# m80-v0_01.net
KiCad netlist of a schematic drawn in EAGLE
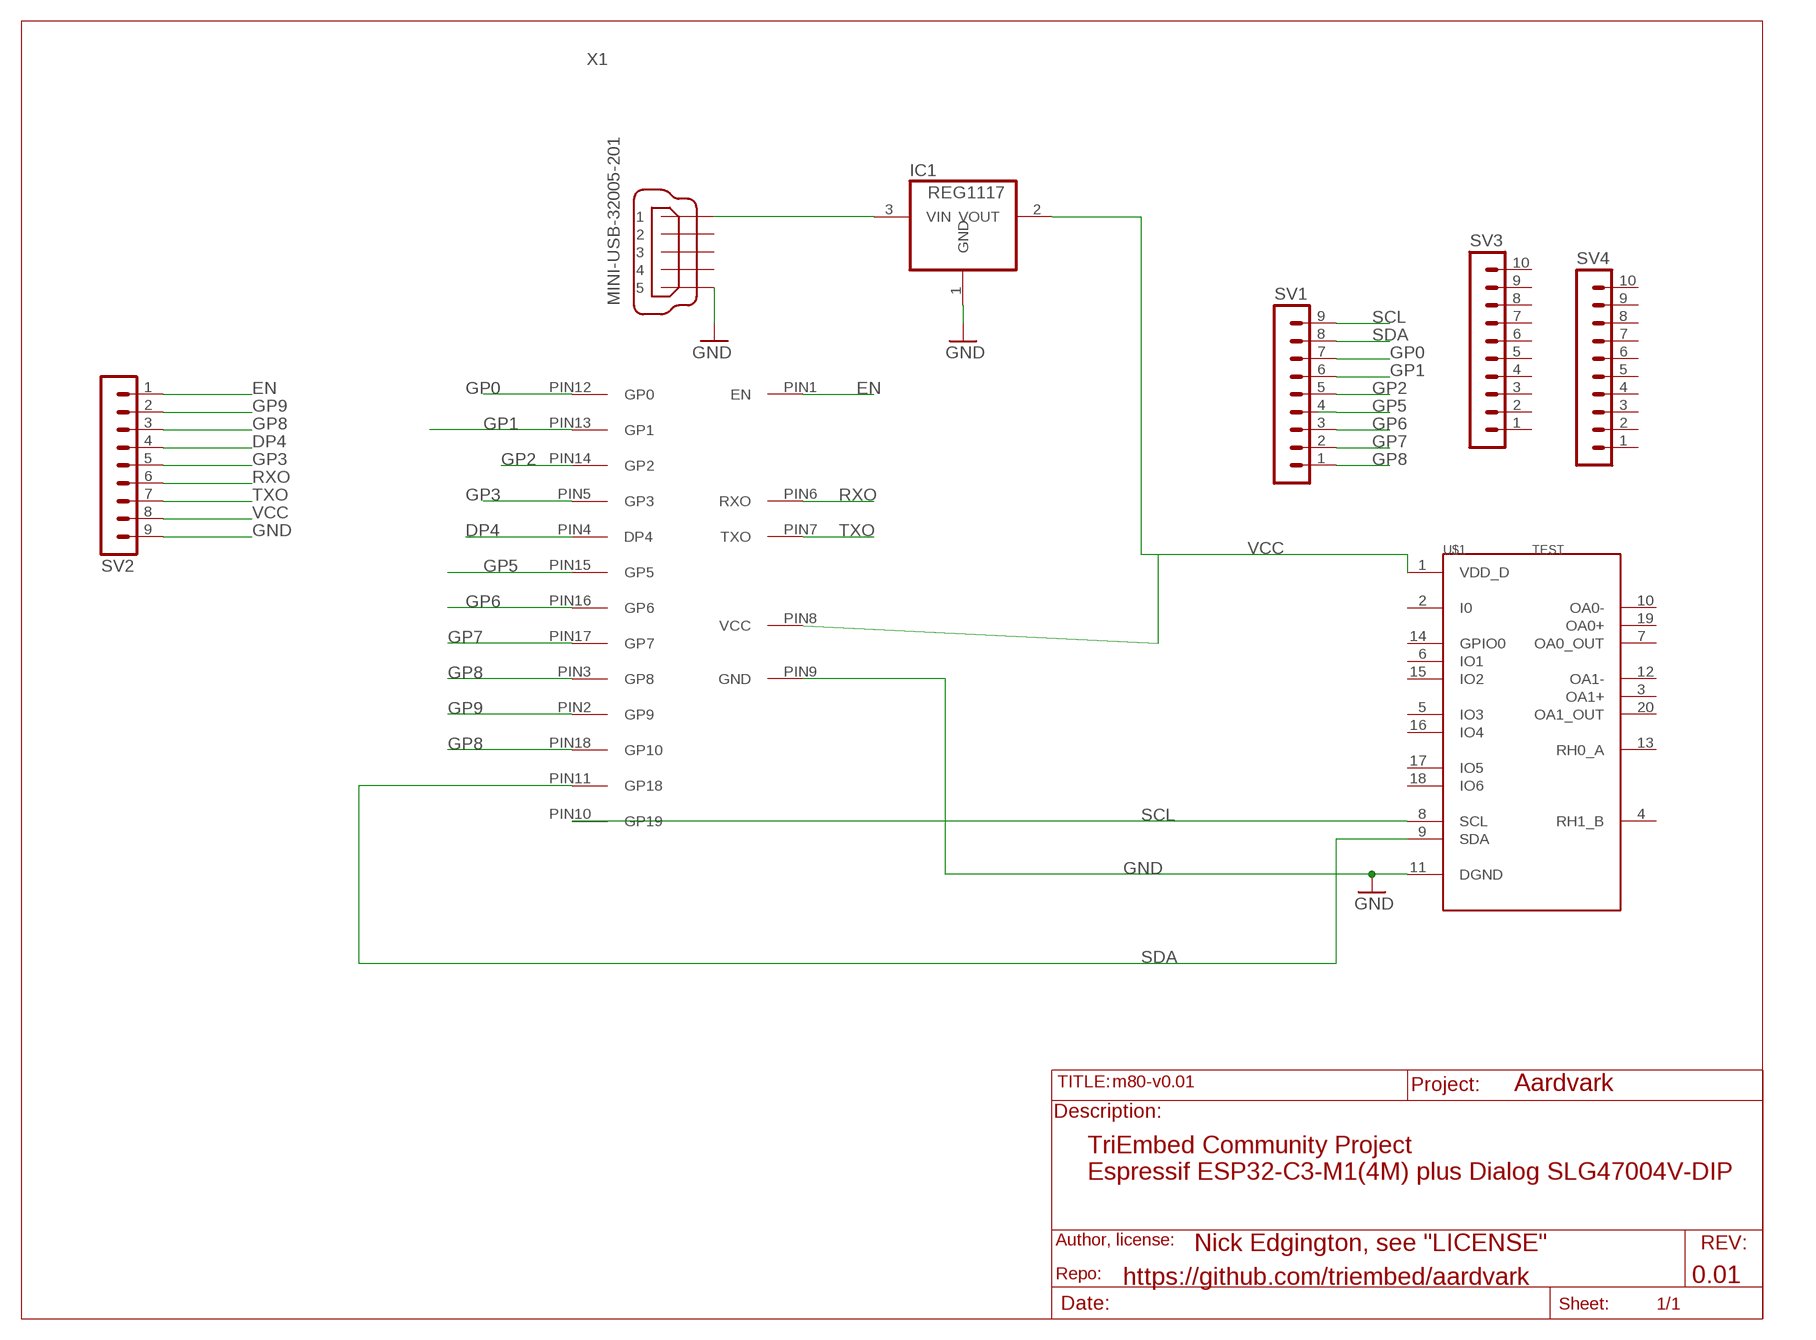
[diagram p0: schematic, sheet 1]

(export (version "E")
  (design (tool "Eeschema 10.0.6"))
  (components
    (comp (ref "IC1")
      (value "REG1117")
      (footprint "eagle-import:SOT223")
      (libsource (lib "eagle-import") (part "REG1117"))
    )
    (comp (ref "SV1")
      (value "MA09-1")
      (footprint "eagle-import:MA09-1")
      (libsource (lib "eagle-import") (part "MA09-1"))
    )
    (comp (ref "SV2")
      (value "MA09-1")
      (footprint "eagle-import:MA09-1")
      (libsource (lib "eagle-import") (part "MA09-1"))
    )
    (comp (ref "SV3")
      (value "MA10-1")
      (footprint "eagle-import:MA10-1")
      (libsource (lib "eagle-import") (part "MA10-1"))
    )
    (comp (ref "SV4")
      (value "MA10-1")
      (footprint "eagle-import:MA10-1")
      (libsource (lib "eagle-import") (part "MA10-1"))
    )
    (comp (ref "U$1")
      (value "TEST")
      (footprint "eagle-import:3M_220-3342-00-0602J_0")
      (libsource (lib "eagle-import") (part "TEST"))
    )
    (comp (ref "U$2")
      (value "ESP32C3")
      (footprint "eagle-import:ESP32-C3-01M")
      (libsource (lib "eagle-import") (part "ESP32C3"))
    )
    (comp (ref "X1")
      (value "MINI-USB-32005-201")
      (footprint "eagle-import:32005-201")
      (libsource (lib "eagle-import") (part "MINI-USB-32005-201"))
    )
  )
  (nets
    (net (code "1") (name "/DP4") (class "Default")
      (node (ref "SV2") (pin "4") (pinfunction "4_4") (pintype "passive"))
      (node (ref "U$2") (pin "PIN4") (pinfunction "DP4_PIN4") (pintype "bidirectional"))
    )
    (net (code "2") (name "/EN") (class "Default")
      (node (ref "SV2") (pin "1") (pinfunction "1_1") (pintype "passive"))
      (node (ref "U$2") (pin "PIN1") (pinfunction "EN_PIN1") (pintype "input"))
    )
    (net (code "3") (name "/GP0") (class "Default")
      (node (ref "SV1") (pin "7") (pinfunction "7_7") (pintype "passive"))
      (node (ref "U$2") (pin "PIN12") (pinfunction "GP0_PIN12") (pintype "bidirectional"))
    )
    (net (code "4") (name "/GP1") (class "Default")
      (node (ref "SV1") (pin "6") (pinfunction "6_6") (pintype "passive"))
      (node (ref "U$2") (pin "PIN13") (pinfunction "GP1_PIN13") (pintype "bidirectional"))
    )
    (net (code "5") (name "/GP2") (class "Default")
      (node (ref "SV1") (pin "5") (pinfunction "5_5") (pintype "passive"))
      (node (ref "U$2") (pin "PIN14") (pinfunction "GP2_PIN14") (pintype "bidirectional"))
    )
    (net (code "6") (name "/GP3") (class "Default")
      (node (ref "SV2") (pin "5") (pinfunction "5_5") (pintype "passive"))
      (node (ref "U$2") (pin "PIN5") (pinfunction "GP3_PIN5") (pintype "bidirectional"))
    )
    (net (code "7") (name "/GP5") (class "Default")
      (node (ref "SV1") (pin "4") (pinfunction "4_4") (pintype "passive"))
      (node (ref "U$2") (pin "PIN15") (pinfunction "GP5_PIN15") (pintype "bidirectional"))
    )
    (net (code "8") (name "/GP6") (class "Default")
      (node (ref "SV1") (pin "3") (pinfunction "3_3") (pintype "passive"))
      (node (ref "U$2") (pin "PIN16") (pinfunction "GP6_PIN16") (pintype "bidirectional"))
    )
    (net (code "9") (name "/GP7") (class "Default")
      (node (ref "SV1") (pin "2") (pinfunction "2_2") (pintype "passive"))
      (node (ref "U$2") (pin "PIN17") (pinfunction "GP7_PIN17") (pintype "bidirectional"))
    )
    (net (code "10") (name "/GP8") (class "Default")
      (node (ref "SV1") (pin "1") (pinfunction "1_1") (pintype "passive"))
      (node (ref "SV2") (pin "3") (pinfunction "3_3") (pintype "passive"))
      (node (ref "U$2") (pin "PIN18") (pinfunction "GP10_PIN18") (pintype "bidirectional"))
      (node (ref "U$2") (pin "PIN3") (pinfunction "GP8_PIN3") (pintype "bidirectional"))
    )
    (net (code "11") (name "/GP9") (class "Default")
      (node (ref "SV2") (pin "2") (pinfunction "2_2") (pintype "passive"))
      (node (ref "U$2") (pin "PIN2") (pinfunction "GP9_PIN2") (pintype "bidirectional"))
    )
    (net (code "12") (name "/RXO") (class "Default")
      (node (ref "SV2") (pin "6") (pinfunction "6_6") (pintype "passive"))
      (node (ref "U$2") (pin "PIN6") (pinfunction "RXO_PIN6") (pintype "bidirectional"))
    )
    (net (code "13") (name "/SCL") (class "Default")
      (node (ref "SV1") (pin "9") (pinfunction "9_9") (pintype "passive"))
      (node (ref "U$1") (pin "8") (pinfunction "SCL_8") (pintype "open_collector"))
      (node (ref "U$2") (pin "PIN10") (pinfunction "GP19_PIN10") (pintype "bidirectional"))
    )
    (net (code "14") (name "/SDA") (class "Default")
      (node (ref "SV1") (pin "8") (pinfunction "8_8") (pintype "passive"))
      (node (ref "U$1") (pin "9") (pinfunction "SDA_9") (pintype "open_collector"))
      (node (ref "U$2") (pin "PIN11") (pinfunction "GP18_PIN11") (pintype "bidirectional"))
    )
    (net (code "15") (name "/TXO") (class "Default")
      (node (ref "SV2") (pin "7") (pinfunction "7_7") (pintype "passive"))
      (node (ref "U$2") (pin "PIN7") (pinfunction "TXO_PIN7") (pintype "bidirectional"))
    )
    (net (code "16") (name "/VCC") (class "Default")
      (node (ref "IC1") (pin "2") (pinfunction "VOUT_2") (pintype "output"))
      (node (ref "SV2") (pin "8") (pinfunction "8_8") (pintype "passive"))
      (node (ref "U$1") (pin "1") (pinfunction "VDD_D_1") (pintype "power_in"))
      (node (ref "U$2") (pin "PIN8") (pinfunction "VCC_PIN8") (pintype "power_in"))
    )
    (net (code "17") (name "GND") (class "Default")
      (node (ref "IC1") (pin "1") (pinfunction "GND_1") (pintype "power_in"))
      (node (ref "SV2") (pin "9") (pinfunction "9_9") (pintype "passive"))
      (node (ref "U$1") (pin "11") (pinfunction "DGND_11") (pintype "power_in"))
      (node (ref "U$2") (pin "PIN9") (pinfunction "GND_PIN9") (pintype "power_in"))
      (node (ref "X1") (pin "5") (pinfunction "5_5") (pintype "passive"))
    )
    (net (code "18") (name "Net-(IC1-VIN)") (class "Default")
      (node (ref "IC1") (pin "3") (pinfunction "VIN_3") (pintype "input"))
      (node (ref "X1") (pin "1") (pinfunction "1_1") (pintype "passive"))
    )
    (net (code "19") (name "unconnected-(SV3-Pad1)") (class "Default")
      (node (ref "SV3") (pin "1") (pinfunction "1_1") (pintype "passive"))
    )
    (net (code "20") (name "unconnected-(SV3-Pad2)") (class "Default")
      (node (ref "SV3") (pin "2") (pinfunction "2_2") (pintype "passive"))
    )
    (net (code "21") (name "unconnected-(SV3-Pad3)") (class "Default")
      (node (ref "SV3") (pin "3") (pinfunction "3_3") (pintype "passive"))
    )
    (net (code "22") (name "unconnected-(SV3-Pad4)") (class "Default")
      (node (ref "SV3") (pin "4") (pinfunction "4_4") (pintype "passive"))
    )
    (net (code "23") (name "unconnected-(SV3-Pad5)") (class "Default")
      (node (ref "SV3") (pin "5") (pinfunction "5_5") (pintype "passive"))
    )
    (net (code "24") (name "unconnected-(SV3-Pad6)") (class "Default")
      (node (ref "SV3") (pin "6") (pinfunction "6_6") (pintype "passive"))
    )
    (net (code "25") (name "unconnected-(SV3-Pad7)") (class "Default")
      (node (ref "SV3") (pin "7") (pinfunction "7_7") (pintype "passive"))
    )
    (net (code "26") (name "unconnected-(SV3-Pad8)") (class "Default")
      (node (ref "SV3") (pin "8") (pinfunction "8_8") (pintype "passive"))
    )
    (net (code "27") (name "unconnected-(SV3-Pad9)") (class "Default")
      (node (ref "SV3") (pin "9") (pinfunction "9_9") (pintype "passive"))
    )
    (net (code "28") (name "unconnected-(SV3-Pad10)") (class "Default")
      (node (ref "SV3") (pin "10") (pinfunction "10_10") (pintype "passive"))
    )
    (net (code "29") (name "unconnected-(SV4-Pad1)") (class "Default")
      (node (ref "SV4") (pin "1") (pinfunction "1_1") (pintype "passive"))
    )
    (net (code "30") (name "unconnected-(SV4-Pad2)") (class "Default")
      (node (ref "SV4") (pin "2") (pinfunction "2_2") (pintype "passive"))
    )
    (net (code "31") (name "unconnected-(SV4-Pad3)") (class "Default")
      (node (ref "SV4") (pin "3") (pinfunction "3_3") (pintype "passive"))
    )
    (net (code "32") (name "unconnected-(SV4-Pad4)") (class "Default")
      (node (ref "SV4") (pin "4") (pinfunction "4_4") (pintype "passive"))
    )
    (net (code "33") (name "unconnected-(SV4-Pad5)") (class "Default")
      (node (ref "SV4") (pin "5") (pinfunction "5_5") (pintype "passive"))
    )
    (net (code "34") (name "unconnected-(SV4-Pad6)") (class "Default")
      (node (ref "SV4") (pin "6") (pinfunction "6_6") (pintype "passive"))
    )
    (net (code "35") (name "unconnected-(SV4-Pad7)") (class "Default")
      (node (ref "SV4") (pin "7") (pinfunction "7_7") (pintype "passive"))
    )
    (net (code "36") (name "unconnected-(SV4-Pad8)") (class "Default")
      (node (ref "SV4") (pin "8") (pinfunction "8_8") (pintype "passive"))
    )
    (net (code "37") (name "unconnected-(SV4-Pad9)") (class "Default")
      (node (ref "SV4") (pin "9") (pinfunction "9_9") (pintype "passive"))
    )
    (net (code "38") (name "unconnected-(SV4-Pad10)") (class "Default")
      (node (ref "SV4") (pin "10") (pinfunction "10_10") (pintype "passive"))
    )
    (net (code "39") (name "unconnected-(U$1-GPIO0-Pad14)") (class "Default")
      (node (ref "U$1") (pin "14") (pinfunction "GPIO0_14") (pintype "bidirectional"))
    )
    (net (code "40") (name "unconnected-(U$1-I0-Pad2)") (class "Default")
      (node (ref "U$1") (pin "2") (pinfunction "I0_2") (pintype "input"))
    )
    (net (code "41") (name "unconnected-(U$1-IO1-Pad6)") (class "Default")
      (node (ref "U$1") (pin "6") (pinfunction "IO1_6") (pintype "bidirectional"))
    )
    (net (code "42") (name "unconnected-(U$1-IO2-Pad15)") (class "Default")
      (node (ref "U$1") (pin "15") (pinfunction "IO2_15") (pintype "bidirectional"))
    )
    (net (code "43") (name "unconnected-(U$1-IO3-Pad5)") (class "Default")
      (node (ref "U$1") (pin "5") (pinfunction "IO3_5") (pintype "bidirectional"))
    )
    (net (code "44") (name "unconnected-(U$1-IO4-Pad16)") (class "Default")
      (node (ref "U$1") (pin "16") (pinfunction "IO4_16") (pintype "bidirectional"))
    )
    (net (code "45") (name "unconnected-(U$1-IO5-Pad17)") (class "Default")
      (node (ref "U$1") (pin "17") (pinfunction "IO5_17") (pintype "bidirectional"))
    )
    (net (code "46") (name "unconnected-(U$1-IO6-Pad18)") (class "Default")
      (node (ref "U$1") (pin "18") (pinfunction "IO6_18") (pintype "bidirectional"))
    )
    (net (code "47") (name "unconnected-(U$1-OA0+-Pad19)") (class "Default")
      (node (ref "U$1") (pin "19") (pinfunction "OA0+_19") (pintype "input"))
    )
    (net (code "48") (name "unconnected-(U$1-OA0--Pad10)") (class "Default")
      (node (ref "U$1") (pin "10") (pinfunction "OA0-_10") (pintype "input"))
    )
    (net (code "49") (name "unconnected-(U$1-OA0_OUT-Pad7)") (class "Default")
      (node (ref "U$1") (pin "7") (pinfunction "OA0_OUT_7") (pintype "input"))
    )
    (net (code "50") (name "unconnected-(U$1-OA1+-Pad3)") (class "Default")
      (node (ref "U$1") (pin "3") (pinfunction "OA1+_3") (pintype "bidirectional"))
    )
    (net (code "51") (name "unconnected-(U$1-OA1--Pad12)") (class "Default")
      (node (ref "U$1") (pin "12") (pinfunction "OA1-_12") (pintype "input"))
    )
    (net (code "52") (name "unconnected-(U$1-OA1_OUT-Pad20)") (class "Default")
      (node (ref "U$1") (pin "20") (pinfunction "OA1_OUT_20") (pintype "output"))
    )
    (net (code "53") (name "unconnected-(U$1-RH0_A-Pad13)") (class "Default")
      (node (ref "U$1") (pin "13") (pinfunction "RH0_A_13") (pintype "passive"))
    )
    (net (code "54") (name "unconnected-(U$1-RH1_B-Pad4)") (class "Default")
      (node (ref "U$1") (pin "4") (pinfunction "RH1_B_4") (pintype "passive"))
    )
    (net (code "55") (name "unconnected-(X1-Pad2)") (class "Default")
      (node (ref "X1") (pin "2") (pinfunction "2_2") (pintype "passive"))
    )
    (net (code "56") (name "unconnected-(X1-Pad3)") (class "Default")
      (node (ref "X1") (pin "3") (pinfunction "3_3") (pintype "passive"))
    )
    (net (code "57") (name "unconnected-(X1-Pad4)") (class "Default")
      (node (ref "X1") (pin "4") (pinfunction "4_4") (pintype "passive"))
    )
  )
)
